# UART.net
KiCad netlist of a schematic drawn in Altium Designer
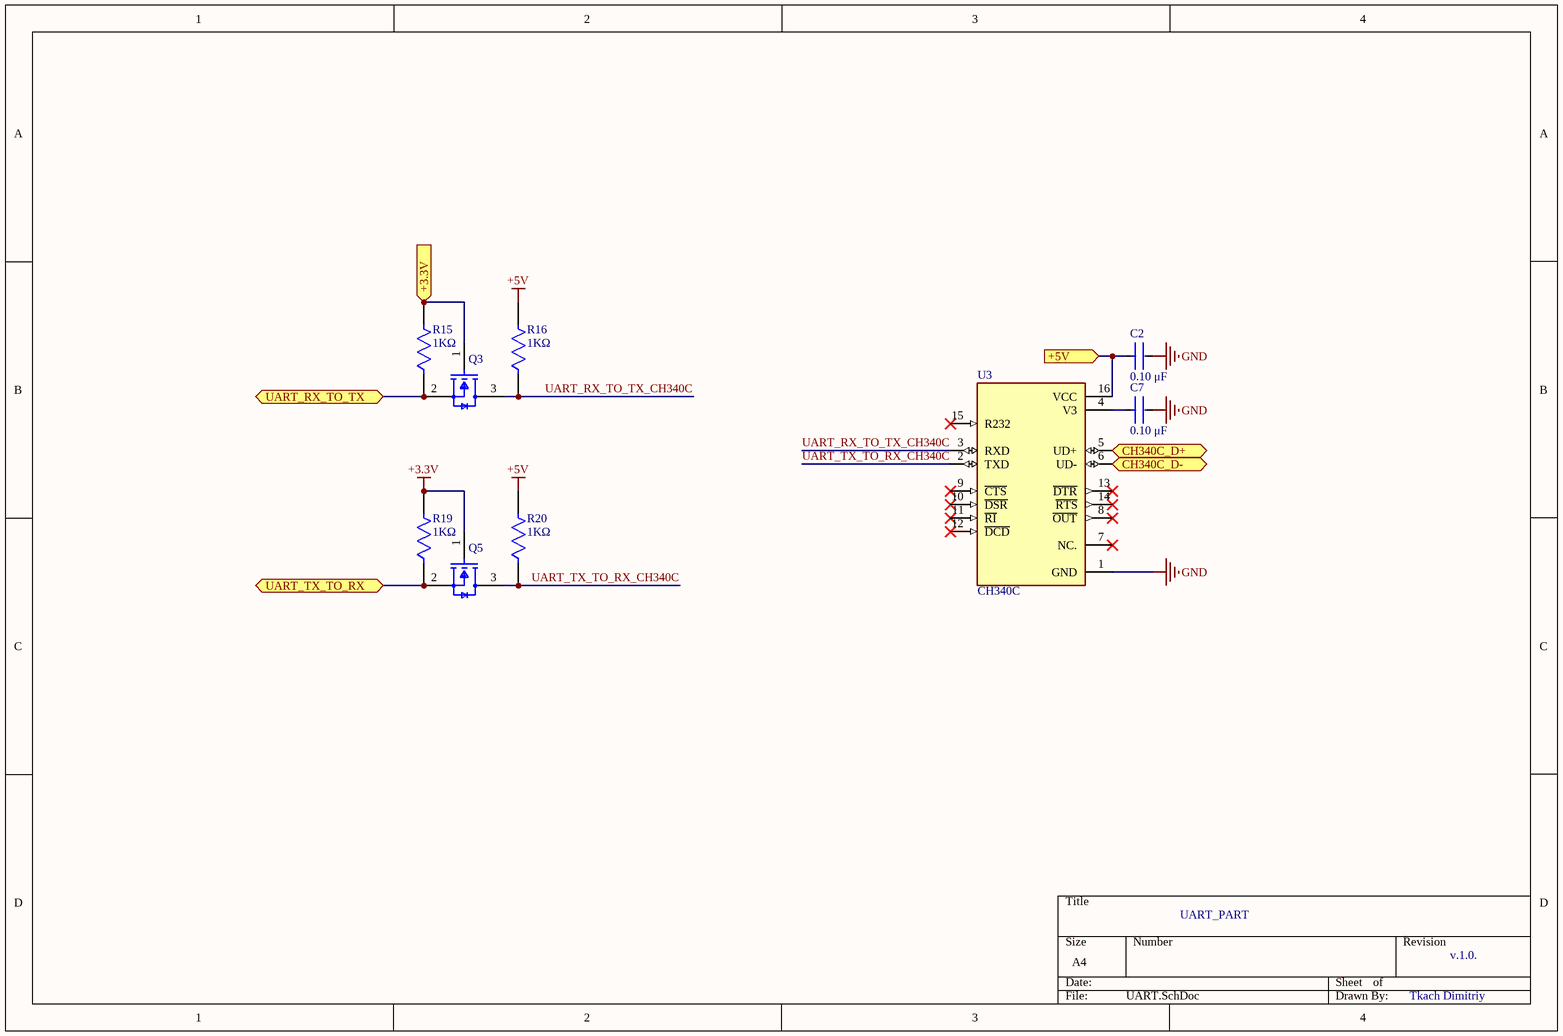
[diagram p0: UART.SchDoc]

(export (version "E")
  (design (tool "Eeschema 10.0.6"))
  (components
    (comp (ref "C2")
      (value "C1206C104K5RACAUTO")
      (footprint "CAPC3216X18M")
      (description "CAP CER 0.1UF 50V X7R 1206")
      (fields
        (field (name "MANUFACTURER") "KEMET")
        (field (name "OCTOPART") "https://octopart.com/c1206c104k5racauto-kemet-12595586")
        (field (name "CAPACITANCE") "0.10 μF")
      )
      (libsource (lib "Internal_Lib_Thermostat_STM8") (part "CMP-03020-005759-1"))
    )
    (comp (ref "C7")
      (value "C1206C104K5RACAUTO")
      (footprint "CAPC3216X18M")
      (description "CAP CER 0.1UF 50V X7R 1206")
      (fields
        (field (name "MANUFACTURER") "KEMET")
        (field (name "OCTOPART") "https://octopart.com/c1206c104k5racauto-kemet-12595586")
        (field (name "CAPACITANCE") "0.10 μF")
      )
      (libsource (lib "Internal_Lib_Thermostat_STM8") (part "CMP-03020-005759-1"))
    )
    (comp (ref "Q3")
      (value "2N7002-7-F")
      (footprint "FP-SOT23-MFG")
      (description "MOSFET N-CH 60V 115MA SOT23-3")
      (fields (field (name "VOLTAGE") "60V"))
      (libsource (lib "Internal_Lib_Thermostat_STM8") (part "3b9c635fedb024a5347a57b145af9cc"))
    )
    (comp (ref "Q5")
      (value "2N7002-7-F")
      (footprint "FP-SOT23-MFG")
      (description "MOSFET N-CH 60V 115MA SOT23-3")
      (fields (field (name "VOLTAGE") "60V"))
      (libsource (lib "Internal_Lib_Thermostat_STM8") (part "3b9c635fedb024a5347a57b145af9cc"))
    )
    (comp (ref "R15")
      (value "1KΩ")
      (footprint "RESC3216X06M")
      (description "CRGCQ1206 1KΩ 0.25W 1% ±100ppm/°C 200V")
      (fields
        (field (name "MANUFACTURER") "TE Connectivity")
        (field (name "MANUFACTURER PART NUMBER") "CRGCQ1206F1K0")
      )
      (libsource (lib "Internal_Lib_Thermostat_STM8") (part "CMP-03211-006592-1"))
    )
    (comp (ref "R16")
      (value "1KΩ")
      (footprint "RESC3216X06M")
      (description "CRGCQ1206 1KΩ 0.25W 1% ±100ppm/°C 200V")
      (fields
        (field (name "MANUFACTURER") "TE Connectivity")
        (field (name "MANUFACTURER PART NUMBER") "CRGCQ1206F1K0")
      )
      (libsource (lib "Internal_Lib_Thermostat_STM8") (part "CMP-03211-006592-1"))
    )
    (comp (ref "R19")
      (value "1KΩ")
      (footprint "RESC3216X06M")
      (description "CRGCQ1206 1KΩ 0.25W 1% ±100ppm/°C 200V")
      (fields
        (field (name "MANUFACTURER") "TE Connectivity")
        (field (name "MANUFACTURER PART NUMBER") "CRGCQ1206F1K0")
      )
      (libsource (lib "Internal_Lib_Thermostat_STM8") (part "CMP-03211-006592-1"))
    )
    (comp (ref "R20")
      (value "1KΩ")
      (footprint "RESC3216X06M")
      (description "CRGCQ1206 1KΩ 0.25W 1% ±100ppm/°C 200V")
      (fields
        (field (name "MANUFACTURER") "TE Connectivity")
        (field (name "MANUFACTURER PART NUMBER") "CRGCQ1206F1K0")
      )
      (libsource (lib "Internal_Lib_Thermostat_STM8") (part "CMP-03211-006592-1"))
    )
    (comp (ref "U3")
      (value "CH340C")
      (footprint "SOIC127P600X180-16N")
      (description "USB to serial chip CH340")
      (fields (field (name "MF") "WCH"))
      (libsource (lib "Internal_Lib_Thermostat_STM8") (part "CMP-019-000000-1"))
    )
  )
  (nets
    (net (code "1") (name "+3.3V") (class "Default")
      (node (ref "Q3") (pin "1") (pinfunction "G_1") (pintype "passive"))
      (node (ref "Q5") (pin "1") (pinfunction "G_1") (pintype "passive"))
      (node (ref "R15") (pin "2") (pinfunction "2_2") (pintype "passive"))
      (node (ref "R19") (pin "2") (pinfunction "2_2") (pintype "passive"))
    )
    (net (code "2") (name "+5V") (class "Default")
      (node (ref "C2") (pin "1") (pinfunction "1_1") (pintype "passive"))
      (node (ref "R16") (pin "2") (pinfunction "2_2") (pintype "passive"))
      (node (ref "R20") (pin "2") (pinfunction "2_2") (pintype "passive"))
      (node (ref "U3") (pin "16") (pinfunction "VCC_16") (pintype "power_in"))
    )
    (net (code "3") (name "/CH340C_D+") (class "Default")
      (node (ref "U3") (pin "5") (pinfunction "UD+_5") (pintype "bidirectional"))
    )
    (net (code "4") (name "/CH340C_D-") (class "Default")
      (node (ref "U3") (pin "6") (pinfunction "UD-_6") (pintype "bidirectional"))
    )
    (net (code "5") (name "/UART_RX_TO_TX") (class "Default")
      (node (ref "Q3") (pin "2") (pinfunction "S_2") (pintype "passive"))
      (node (ref "R15") (pin "1") (pinfunction "1_1") (pintype "passive"))
    )
    (net (code "6") (name "/UART_RX_TO_TX_CH340C") (class "Default")
      (node (ref "Q3") (pin "3") (pinfunction "D_3") (pintype "passive"))
      (node (ref "R16") (pin "1") (pinfunction "1_1") (pintype "passive"))
      (node (ref "U3") (pin "3") (pinfunction "RXD_3") (pintype "bidirectional"))
    )
    (net (code "7") (name "/UART_TX_TO_RX") (class "Default")
      (node (ref "Q5") (pin "2") (pinfunction "S_2") (pintype "passive"))
      (node (ref "R19") (pin "1") (pinfunction "1_1") (pintype "passive"))
    )
    (net (code "8") (name "/UART_TX_TO_RX_CH340C") (class "Default")
      (node (ref "Q5") (pin "3") (pinfunction "D_3") (pintype "passive"))
      (node (ref "R20") (pin "1") (pinfunction "1_1") (pintype "passive"))
      (node (ref "U3") (pin "2") (pinfunction "TXD_2") (pintype "bidirectional"))
    )
    (net (code "9") (name "GND") (class "Default")
      (node (ref "C2") (pin "2") (pinfunction "2_2") (pintype "passive"))
      (node (ref "C7") (pin "2") (pinfunction "2_2") (pintype "passive"))
      (node (ref "U3") (pin "1") (pinfunction "GND_1") (pintype "power_in"))
    )
    (net (code "10") (name "Net-(U3-V3)") (class "Default")
      (node (ref "C7") (pin "1") (pinfunction "1_1") (pintype "passive"))
      (node (ref "U3") (pin "4") (pinfunction "V3_4") (pintype "power_in"))
    )
    (net (code "11") (name "unconnected-(U3-NC.-Pad7)") (class "Default")
      (node (ref "U3") (pin "7") (pinfunction "NC._7") (pintype "passive+no_connect"))
    )
    (net (code "12") (name "unconnected-(U3-R232-Pad15)") (class "Default")
      (node (ref "U3") (pin "15") (pinfunction "R232_15") (pintype "input+no_connect"))
    )
    (net (code "13") (name "unconnected-(U3-~{CTS}-Pad9)") (class "Default")
      (node (ref "U3") (pin "9") (pinfunction "~{CTS}_9") (pintype "input+no_connect"))
    )
    (net (code "14") (name "unconnected-(U3-~{DCD}-Pad12)") (class "Default")
      (node (ref "U3") (pin "12") (pinfunction "~{DCD}_12") (pintype "input+no_connect"))
    )
    (net (code "15") (name "unconnected-(U3-~{DSR}-Pad10)") (class "Default")
      (node (ref "U3") (pin "10") (pinfunction "~{DSR}_10") (pintype "input+no_connect"))
    )
    (net (code "16") (name "unconnected-(U3-~{DTR}-Pad13)") (class "Default")
      (node (ref "U3") (pin "13") (pinfunction "~{DTR}_13") (pintype "output+no_connect"))
    )
    (net (code "17") (name "unconnected-(U3-~{OUT}-Pad8)") (class "Default")
      (node (ref "U3") (pin "8") (pinfunction "~{OUT}_8") (pintype "output+no_connect"))
    )
    (net (code "18") (name "unconnected-(U3-~{RI}-Pad11)") (class "Default")
      (node (ref "U3") (pin "11") (pinfunction "~{RI}_11") (pintype "input+no_connect"))
    )
    (net (code "19") (name "unconnected-(U3-~{RTS}-Pad14)") (class "Default")
      (node (ref "U3") (pin "14") (pinfunction "~{RTS}_14") (pintype "output+no_connect"))
    )
  )
)
